# besc_mcu_sch.net
KiCad netlist of a schematic drawn in Altium Designer
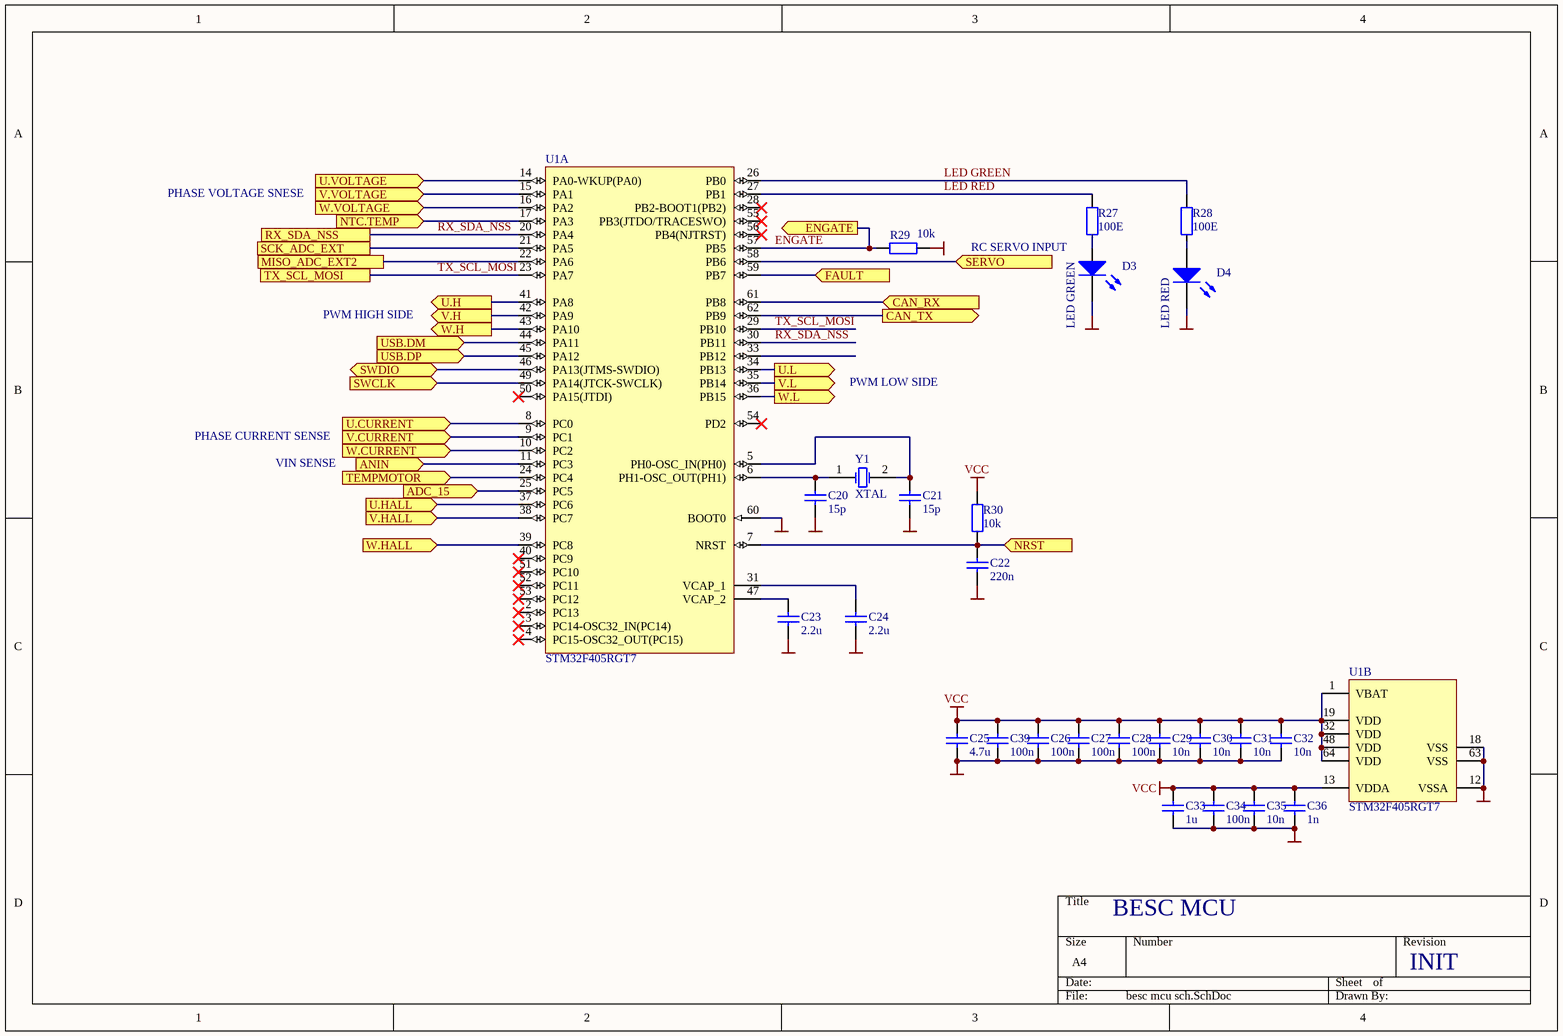
[diagram p0: besc mcu sch.SchDoc]

(export (version "E")
  (design (tool "Eeschema 10.0.6"))
  (components
    (comp (ref "C20")
      (value "15p")
      (footprint "0603")
      (description "Capacitor")
      (fields (field (name "PUBLISHER") "Altium Limited"))
      (libsource (lib "Miscellaneous Devices") (part "Cap"))
    )
    (comp (ref "C21")
      (value "15p")
      (footprint "0603")
      (description "Capacitor")
      (fields (field (name "PUBLISHER") "Altium Limited"))
      (libsource (lib "Miscellaneous Devices") (part "Cap"))
    )
    (comp (ref "C22")
      (value "220n")
      (footprint "0603")
      (description "Capacitor")
      (fields (field (name "PUBLISHER") "Altium Limited"))
      (libsource (lib "Miscellaneous Devices") (part "Cap"))
    )
    (comp (ref "C23")
      (value "2.2u")
      (footprint "0603")
      (description "Capacitor")
      (fields (field (name "PUBLISHER") "Altium Limited"))
      (libsource (lib "Miscellaneous Devices") (part "Cap"))
    )
    (comp (ref "C24")
      (value "2.2u")
      (footprint "0603")
      (description "Capacitor")
      (fields (field (name "PUBLISHER") "Altium Limited"))
      (libsource (lib "Miscellaneous Devices") (part "Cap"))
    )
    (comp (ref "C25")
      (value "4.7u")
      (footprint "0603")
      (description "Capacitor")
      (fields (field (name "PUBLISHER") "Altium Limited"))
      (libsource (lib "Miscellaneous Devices") (part "Cap"))
    )
    (comp (ref "C26")
      (value "100n")
      (footprint "0603")
      (description "Capacitor")
      (fields (field (name "PUBLISHER") "Altium Limited"))
      (libsource (lib "Miscellaneous Devices") (part "Cap"))
    )
    (comp (ref "C27")
      (value "100n")
      (footprint "0603")
      (description "Capacitor")
      (fields (field (name "PUBLISHER") "Altium Limited"))
      (libsource (lib "Miscellaneous Devices") (part "Cap"))
    )
    (comp (ref "C28")
      (value "100n")
      (footprint "0603")
      (description "Capacitor")
      (fields (field (name "PUBLISHER") "Altium Limited"))
      (libsource (lib "Miscellaneous Devices") (part "Cap"))
    )
    (comp (ref "C29")
      (value "10n")
      (footprint "0603")
      (description "Capacitor")
      (fields (field (name "PUBLISHER") "Altium Limited"))
      (libsource (lib "Miscellaneous Devices") (part "Cap"))
    )
    (comp (ref "C30")
      (value "10n")
      (footprint "0603")
      (description "Capacitor")
      (fields (field (name "PUBLISHER") "Altium Limited"))
      (libsource (lib "Miscellaneous Devices") (part "Cap"))
    )
    (comp (ref "C31")
      (value "10n")
      (footprint "0603")
      (description "Capacitor")
      (fields (field (name "PUBLISHER") "Altium Limited"))
      (libsource (lib "Miscellaneous Devices") (part "Cap"))
    )
    (comp (ref "C32")
      (value "10n")
      (footprint "0603")
      (description "Capacitor")
      (fields (field (name "PUBLISHER") "Altium Limited"))
      (libsource (lib "Miscellaneous Devices") (part "Cap"))
    )
    (comp (ref "C33")
      (value "1u")
      (footprint "0603")
      (description "Capacitor")
      (fields (field (name "PUBLISHER") "Altium Limited"))
      (libsource (lib "Miscellaneous Devices") (part "Cap"))
    )
    (comp (ref "C34")
      (value "100n")
      (footprint "0603")
      (description "Capacitor")
      (fields (field (name "PUBLISHER") "Altium Limited"))
      (libsource (lib "Miscellaneous Devices") (part "Cap"))
    )
    (comp (ref "C35")
      (value "10n")
      (footprint "0603")
      (description "Capacitor")
      (fields (field (name "PUBLISHER") "Altium Limited"))
      (libsource (lib "Miscellaneous Devices") (part "Cap"))
    )
    (comp (ref "C36")
      (value "1n")
      (footprint "0603")
      (description "Capacitor")
      (fields (field (name "PUBLISHER") "Altium Limited"))
      (libsource (lib "Miscellaneous Devices") (part "Cap"))
    )
    (comp (ref "C39")
      (value "100n")
      (footprint "0603")
      (description "Capacitor")
      (fields (field (name "PUBLISHER") "Altium Limited"))
      (libsource (lib "Miscellaneous Devices") (part "Cap"))
    )
    (comp (ref "D3")
      (value "LED GREEN")
      (footprint "0805-diode")
      (description "Typical INFRARED GaAs LED")
      (fields (field (name "PUBLISHER") "Altium Limited"))
      (libsource (lib "Miscellaneous Devices") (part "LED0"))
    )
    (comp (ref "D4")
      (value "LED RED")
      (footprint "0805-diode")
      (description "Typical INFRARED GaAs LED")
      (fields (field (name "PUBLISHER") "Altium Limited"))
      (libsource (lib "Miscellaneous Devices") (part "LED0"))
    )
    (comp (ref "R27")
      (value "100E")
      (footprint "0603")
      (description "Resistor")
      (fields (field (name "PUBLISHER") "Altium Limited"))
      (libsource (lib "Miscellaneous Devices") (part "Res2"))
    )
    (comp (ref "R28")
      (value "100E")
      (footprint "0603")
      (description "Resistor")
      (fields (field (name "PUBLISHER") "Altium Limited"))
      (libsource (lib "Miscellaneous Devices") (part "Res2"))
    )
    (comp (ref "R29")
      (value "10k")
      (footprint "0603")
      (description "Resistor")
      (fields (field (name "PUBLISHER") "Altium Limited"))
      (libsource (lib "") (part "Res2_1"))
    )
    (comp (ref "R30")
      (value "10k")
      (footprint "0603")
      (description "Resistor")
      (fields (field (name "PUBLISHER") "Altium Limited"))
      (libsource (lib "Miscellaneous Devices") (part "Res2"))
    )
    (comp (ref "U1")
      (value "STM32F405RGT7")
      (footprint "STM-LQFP64_N")
      (fields (field (name "MANUFACTURER") "STMicroelectronics"))
      (libsource (lib "STMicroelectronics STM32 F4") (part "STM32F405RGT7"))
    )
    (comp (ref "Y1")
      (value "XTAL")
      (footprint "XTAL 5 x 3.2 mm")
      (description "Crystal Oscillator")
      (fields (field (name "PUBLISHER") "Altium Limited"))
      (libsource (lib "Miscellaneous Devices") (part "XTAL"))
    )
  )
  (nets
    (net (code "1") (name "/ADC_15") (class "Default")
      (node (ref "U1") (pin "25") (pinfunction "PC5_25") (pintype "bidirectional"))
    )
    (net (code "2") (name "/ANIN") (class "Default")
      (node (ref "U1") (pin "11") (pinfunction "PC3_11") (pintype "bidirectional"))
    )
    (net (code "3") (name "/CAN_RX") (class "Default")
      (node (ref "U1") (pin "61") (pinfunction "PB8_61") (pintype "bidirectional"))
    )
    (net (code "4") (name "/CAN_TX") (class "Default")
      (node (ref "U1") (pin "62") (pinfunction "PB9_62") (pintype "bidirectional"))
    )
    (net (code "5") (name "/ENGATE") (class "Default")
      (node (ref "R29") (pin "1") (pinfunction "1_1") (pintype "passive"))
      (node (ref "U1") (pin "57") (pinfunction "PB5_57") (pintype "bidirectional"))
    )
    (net (code "6") (name "/FAULT") (class "Default")
      (node (ref "U1") (pin "59") (pinfunction "PB7_59") (pintype "bidirectional"))
    )
    (net (code "7") (name "/LED GREEN") (class "Default")
      (node (ref "R28") (pin "1") (pinfunction "1_1") (pintype "passive"))
      (node (ref "U1") (pin "26") (pinfunction "PB0_26") (pintype "bidirectional"))
    )
    (net (code "8") (name "/LED RED") (class "Default")
      (node (ref "R27") (pin "1") (pinfunction "1_1") (pintype "passive"))
      (node (ref "U1") (pin "27") (pinfunction "PB1_27") (pintype "bidirectional"))
    )
    (net (code "9") (name "/MISO_ADC_EXT2") (class "Default")
      (node (ref "U1") (pin "22") (pinfunction "PA6_22") (pintype "bidirectional"))
    )
    (net (code "10") (name "/NRST") (class "Default")
      (node (ref "C22") (pin "2") (pinfunction "2_2") (pintype "passive"))
      (node (ref "R30") (pin "2") (pinfunction "2_2") (pintype "passive"))
      (node (ref "U1") (pin "7") (pinfunction "NRST_7") (pintype "bidirectional"))
    )
    (net (code "11") (name "/NTC.TEMP") (class "Default")
      (node (ref "U1") (pin "17") (pinfunction "PA3_17") (pintype "bidirectional"))
    )
    (net (code "12") (name "/RX_SDA_NSS") (class "Default")
      (node (ref "U1") (pin "20") (pinfunction "PA4_20") (pintype "bidirectional"))
      (node (ref "U1") (pin "30") (pinfunction "PB11_30") (pintype "bidirectional"))
    )
    (net (code "13") (name "/SCK_ADC_EXT") (class "Default")
      (node (ref "U1") (pin "21") (pinfunction "PA5_21") (pintype "bidirectional"))
    )
    (net (code "14") (name "/SERVO") (class "Default")
      (node (ref "U1") (pin "58") (pinfunction "PB6_58") (pintype "bidirectional"))
    )
    (net (code "15") (name "/SWCLK") (class "Default")
      (node (ref "U1") (pin "49") (pinfunction "PA14(JTCK-SWCLK)_49") (pintype "bidirectional"))
    )
    (net (code "16") (name "/SWDIO") (class "Default")
      (node (ref "U1") (pin "46") (pinfunction "PA13(JTMS-SWDIO)_46") (pintype "bidirectional"))
    )
    (net (code "17") (name "/TEMPMOTOR") (class "Default")
      (node (ref "U1") (pin "24") (pinfunction "PC4_24") (pintype "bidirectional"))
    )
    (net (code "18") (name "/TX_SCL_MOSI") (class "Default")
      (node (ref "U1") (pin "23") (pinfunction "PA7_23") (pintype "bidirectional"))
      (node (ref "U1") (pin "29") (pinfunction "PB10_29") (pintype "bidirectional"))
    )
    (net (code "19") (name "/U.CURRENT") (class "Default")
      (node (ref "U1") (pin "8") (pinfunction "PC0_8") (pintype "bidirectional"))
    )
    (net (code "20") (name "/U.H") (class "Default")
      (node (ref "U1") (pin "41") (pinfunction "PA8_41") (pintype "bidirectional"))
    )
    (net (code "21") (name "/U.HALL") (class "Default")
      (node (ref "U1") (pin "37") (pinfunction "PC6_37") (pintype "bidirectional"))
    )
    (net (code "22") (name "/U.L") (class "Default")
      (node (ref "U1") (pin "34") (pinfunction "PB13_34") (pintype "bidirectional"))
    )
    (net (code "23") (name "/U.VOLTAGE") (class "Default")
      (node (ref "U1") (pin "14") (pinfunction "PA0-WKUP(PA0)_14") (pintype "bidirectional"))
    )
    (net (code "24") (name "/USB.DM") (class "Default")
      (node (ref "U1") (pin "44") (pinfunction "PA11_44") (pintype "bidirectional"))
    )
    (net (code "25") (name "/USB.DP") (class "Default")
      (node (ref "U1") (pin "45") (pinfunction "PA12_45") (pintype "bidirectional"))
    )
    (net (code "26") (name "/V.CURRENT") (class "Default")
      (node (ref "U1") (pin "9") (pinfunction "PC1_9") (pintype "bidirectional"))
    )
    (net (code "27") (name "/V.H") (class "Default")
      (node (ref "U1") (pin "42") (pinfunction "PA9_42") (pintype "bidirectional"))
    )
    (net (code "28") (name "/V.HALL") (class "Default")
      (node (ref "U1") (pin "38") (pinfunction "PC7_38") (pintype "bidirectional"))
    )
    (net (code "29") (name "/V.L") (class "Default")
      (node (ref "U1") (pin "35") (pinfunction "PB14_35") (pintype "bidirectional"))
    )
    (net (code "30") (name "/V.VOLTAGE") (class "Default")
      (node (ref "U1") (pin "15") (pinfunction "PA1_15") (pintype "bidirectional"))
    )
    (net (code "31") (name "/W.CURRENT") (class "Default")
      (node (ref "U1") (pin "10") (pinfunction "PC2_10") (pintype "bidirectional"))
    )
    (net (code "32") (name "/W.H") (class "Default")
      (node (ref "U1") (pin "43") (pinfunction "PA10_43") (pintype "bidirectional"))
    )
    (net (code "33") (name "/W.HALL") (class "Default")
      (node (ref "U1") (pin "39") (pinfunction "PC8_39") (pintype "bidirectional"))
    )
    (net (code "34") (name "/W.L") (class "Default")
      (node (ref "U1") (pin "36") (pinfunction "PB15_36") (pintype "bidirectional"))
    )
    (net (code "35") (name "/W.VOLTAGE") (class "Default")
      (node (ref "U1") (pin "16") (pinfunction "PA2_16") (pintype "bidirectional"))
    )
    (net (code "36") (name "LGND") (class "Default")
      (node (ref "C20") (pin "1") (pinfunction "1_1") (pintype "passive"))
      (node (ref "C21") (pin "1") (pinfunction "1_1") (pintype "passive"))
      (node (ref "C22") (pin "1") (pinfunction "1_1") (pintype "passive"))
      (node (ref "C23") (pin "1") (pinfunction "1_1") (pintype "passive"))
      (node (ref "C24") (pin "1") (pinfunction "1_1") (pintype "passive"))
      (node (ref "C25") (pin "1") (pinfunction "1_1") (pintype "passive"))
      (node (ref "C26") (pin "1") (pinfunction "1_1") (pintype "passive"))
      (node (ref "C27") (pin "1") (pinfunction "1_1") (pintype "passive"))
      (node (ref "C28") (pin "1") (pinfunction "1_1") (pintype "passive"))
      (node (ref "C29") (pin "1") (pinfunction "1_1") (pintype "passive"))
      (node (ref "C30") (pin "1") (pinfunction "1_1") (pintype "passive"))
      (node (ref "C31") (pin "1") (pinfunction "1_1") (pintype "passive"))
      (node (ref "C32") (pin "1") (pinfunction "1_1") (pintype "passive"))
      (node (ref "C33") (pin "1") (pinfunction "1_1") (pintype "passive"))
      (node (ref "C34") (pin "1") (pinfunction "1_1") (pintype "passive"))
      (node (ref "C35") (pin "1") (pinfunction "1_1") (pintype "passive"))
      (node (ref "C36") (pin "1") (pinfunction "1_1") (pintype "passive"))
      (node (ref "C39") (pin "1") (pinfunction "1_1") (pintype "passive"))
      (node (ref "D3") (pin "2") (pinfunction "K_2") (pintype "passive"))
      (node (ref "D4") (pin "2") (pinfunction "K_2") (pintype "passive"))
      (node (ref "R29") (pin "2") (pinfunction "2_2") (pintype "passive"))
      (node (ref "U1") (pin "12") (pinfunction "VSSA_12") (pintype "power_in"))
      (node (ref "U1") (pin "18") (pinfunction "VSS_18") (pintype "power_in"))
      (node (ref "U1") (pin "60") (pinfunction "BOOT0_60") (pintype "input"))
      (node (ref "U1") (pin "63") (pinfunction "VSS_63") (pintype "power_in"))
    )
    (net (code "37") (name "Net-(D3-A)") (class "Default")
      (node (ref "D3") (pin "1") (pinfunction "A_1") (pintype "passive"))
      (node (ref "R27") (pin "2") (pinfunction "2_2") (pintype "passive"))
    )
    (net (code "38") (name "Net-(D4-A)") (class "Default")
      (node (ref "D4") (pin "1") (pinfunction "A_1") (pintype "passive"))
      (node (ref "R28") (pin "2") (pinfunction "2_2") (pintype "passive"))
    )
    (net (code "39") (name "Net-(U1A-PH0-OSC_IN(PH0))") (class "Default")
      (node (ref "C21") (pin "2") (pinfunction "2_2") (pintype "passive"))
      (node (ref "U1") (pin "5") (pinfunction "PH0-OSC_IN(PH0)_5") (pintype "bidirectional"))
      (node (ref "Y1") (pin "2") (pinfunction "OSC2_2") (pintype "passive"))
    )
    (net (code "40") (name "Net-(U1A-PH1-OSC_OUT(PH1))") (class "Default")
      (node (ref "C20") (pin "2") (pinfunction "2_2") (pintype "passive"))
      (node (ref "U1") (pin "6") (pinfunction "PH1-OSC_OUT(PH1)_6") (pintype "bidirectional"))
      (node (ref "Y1") (pin "1") (pinfunction "OSC1_1") (pintype "passive"))
    )
    (net (code "41") (name "Net-(U1A-VCAP_1)") (class "Default")
      (node (ref "C24") (pin "2") (pinfunction "2_2") (pintype "passive"))
      (node (ref "U1") (pin "31") (pinfunction "VCAP_1_31") (pintype "power_in"))
    )
    (net (code "42") (name "Net-(U1A-VCAP_2)") (class "Default")
      (node (ref "C23") (pin "2") (pinfunction "2_2") (pintype "passive"))
      (node (ref "U1") (pin "47") (pinfunction "VCAP_2_47") (pintype "power_in"))
    )
    (net (code "43") (name "VCC") (class "Default")
      (node (ref "C25") (pin "2") (pinfunction "2_2") (pintype "passive"))
      (node (ref "C26") (pin "2") (pinfunction "2_2") (pintype "passive"))
      (node (ref "C27") (pin "2") (pinfunction "2_2") (pintype "passive"))
      (node (ref "C28") (pin "2") (pinfunction "2_2") (pintype "passive"))
      (node (ref "C29") (pin "2") (pinfunction "2_2") (pintype "passive"))
      (node (ref "C30") (pin "2") (pinfunction "2_2") (pintype "passive"))
      (node (ref "C31") (pin "2") (pinfunction "2_2") (pintype "passive"))
      (node (ref "C32") (pin "2") (pinfunction "2_2") (pintype "passive"))
      (node (ref "C33") (pin "2") (pinfunction "2_2") (pintype "passive"))
      (node (ref "C34") (pin "2") (pinfunction "2_2") (pintype "passive"))
      (node (ref "C35") (pin "2") (pinfunction "2_2") (pintype "passive"))
      (node (ref "C36") (pin "2") (pinfunction "2_2") (pintype "passive"))
      (node (ref "C39") (pin "2") (pinfunction "2_2") (pintype "passive"))
      (node (ref "R30") (pin "1") (pinfunction "1_1") (pintype "passive"))
      (node (ref "U1") (pin "1") (pinfunction "VBAT_1") (pintype "power_in"))
      (node (ref "U1") (pin "13") (pinfunction "VDDA_13") (pintype "power_in"))
      (node (ref "U1") (pin "19") (pinfunction "VDD_19") (pintype "power_in"))
      (node (ref "U1") (pin "32") (pinfunction "VDD_32") (pintype "power_in"))
      (node (ref "U1") (pin "48") (pinfunction "VDD_48") (pintype "power_in"))
      (node (ref "U1") (pin "64") (pinfunction "VDD_64") (pintype "power_in"))
    )
    (net (code "44") (name "unconnected-(U1A-PA15(JTDI)-Pad50)") (class "Default")
      (node (ref "U1") (pin "50") (pinfunction "PA15(JTDI)_50") (pintype "bidirectional+no_connect"))
    )
    (net (code "45") (name "unconnected-(U1A-PB2-BOOT1(PB2)-Pad28)") (class "Default")
      (node (ref "U1") (pin "28") (pinfunction "PB2-BOOT1(PB2)_28") (pintype "bidirectional+no_connect"))
    )
    (net (code "46") (name "unconnected-(U1A-PB3(JTDO{slash}TRACESWO)-Pad55)") (class "Default")
      (node (ref "U1") (pin "55") (pinfunction "PB3(JTDO/TRACESWO)_55") (pintype "bidirectional+no_connect"))
    )
    (net (code "47") (name "unconnected-(U1A-PB4(NJTRST)-Pad56)") (class "Default")
      (node (ref "U1") (pin "56") (pinfunction "PB4(NJTRST)_56") (pintype "bidirectional+no_connect"))
    )
    (net (code "48") (name "unconnected-(U1A-PB12-Pad33)") (class "Default")
      (node (ref "U1") (pin "33") (pinfunction "PB12_33") (pintype "bidirectional"))
    )
    (net (code "49") (name "unconnected-(U1A-PC9-Pad40)") (class "Default")
      (node (ref "U1") (pin "40") (pinfunction "PC9_40") (pintype "bidirectional+no_connect"))
    )
    (net (code "50") (name "unconnected-(U1A-PC10-Pad51)") (class "Default")
      (node (ref "U1") (pin "51") (pinfunction "PC10_51") (pintype "bidirectional+no_connect"))
    )
    (net (code "51") (name "unconnected-(U1A-PC11-Pad52)") (class "Default")
      (node (ref "U1") (pin "52") (pinfunction "PC11_52") (pintype "bidirectional+no_connect"))
    )
    (net (code "52") (name "unconnected-(U1A-PC12-Pad53)") (class "Default")
      (node (ref "U1") (pin "53") (pinfunction "PC12_53") (pintype "bidirectional+no_connect"))
    )
    (net (code "53") (name "unconnected-(U1A-PC13-Pad2)") (class "Default")
      (node (ref "U1") (pin "2") (pinfunction "PC13_2") (pintype "bidirectional+no_connect"))
    )
    (net (code "54") (name "unconnected-(U1A-PC14-OSC32_IN(PC14)-Pad3)") (class "Default")
      (node (ref "U1") (pin "3") (pinfunction "PC14-OSC32_IN(PC14)_3") (pintype "bidirectional+no_connect"))
    )
    (net (code "55") (name "unconnected-(U1A-PC15-OSC32_OUT(PC15)-Pad4)") (class "Default")
      (node (ref "U1") (pin "4") (pinfunction "PC15-OSC32_OUT(PC15)_4") (pintype "bidirectional+no_connect"))
    )
    (net (code "56") (name "unconnected-(U1A-PD2-Pad54)") (class "Default")
      (node (ref "U1") (pin "54") (pinfunction "PD2_54") (pintype "bidirectional+no_connect"))
    )
  )
)
